# 00_POWER.net
KiCad netlist of a schematic drawn in Altium Designer
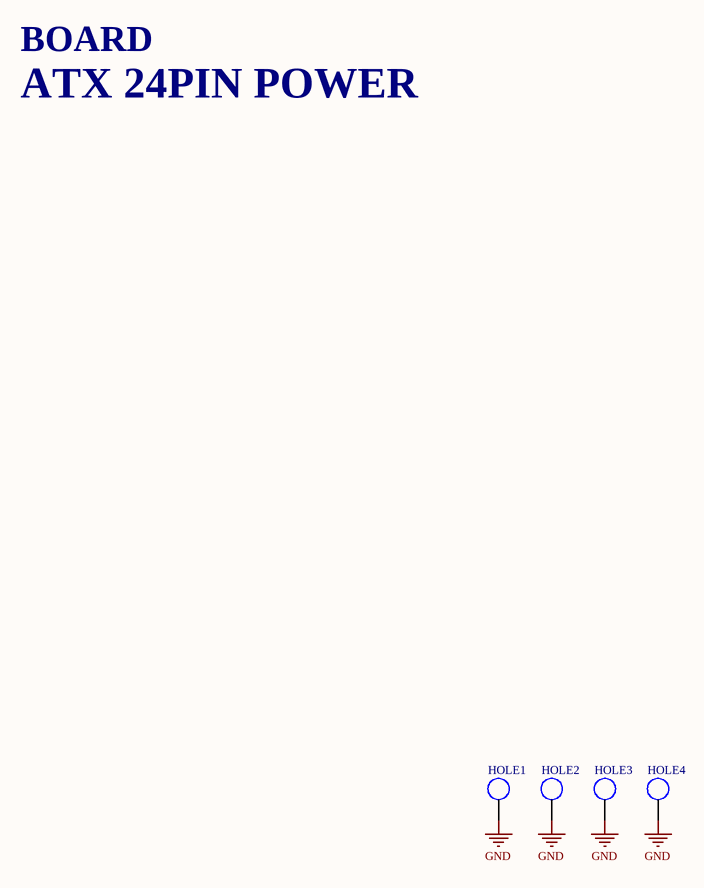
[diagram p0: 00_POWER.SchDoc]

(export (version "E")
  (design (tool "Eeschema 10.0.6"))
  (components
    (comp (ref "HOLE1")
      (value "LOADHOLE")
      (footprint "LOADHOLE")
      (libsource (lib "MotherBoard") (part "LOADHOLE"))
    )
    (comp (ref "HOLE2")
      (value "LOADHOLE")
      (footprint "LOADHOLE")
      (libsource (lib "MotherBoard") (part "LOADHOLE"))
    )
    (comp (ref "HOLE3")
      (value "LOADHOLE")
      (footprint "LOADHOLE")
      (libsource (lib "MotherBoard") (part "LOADHOLE"))
    )
    (comp (ref "HOLE4")
      (value "LOADHOLE")
      (footprint "LOADHOLE")
      (libsource (lib "MotherBoard") (part "LOADHOLE"))
    )
  )
  (nets
    (net (code "1") (name "GND") (class "Default")
      (node (ref "HOLE1") (pin "1") (pintype "passive"))
      (node (ref "HOLE2") (pin "1") (pintype "passive"))
      (node (ref "HOLE3") (pin "1") (pintype "passive"))
      (node (ref "HOLE4") (pin "1") (pintype "passive"))
    )
  )
)
